# RCShield-v3.net
KiCad netlist of a schematic drawn in EAGLE
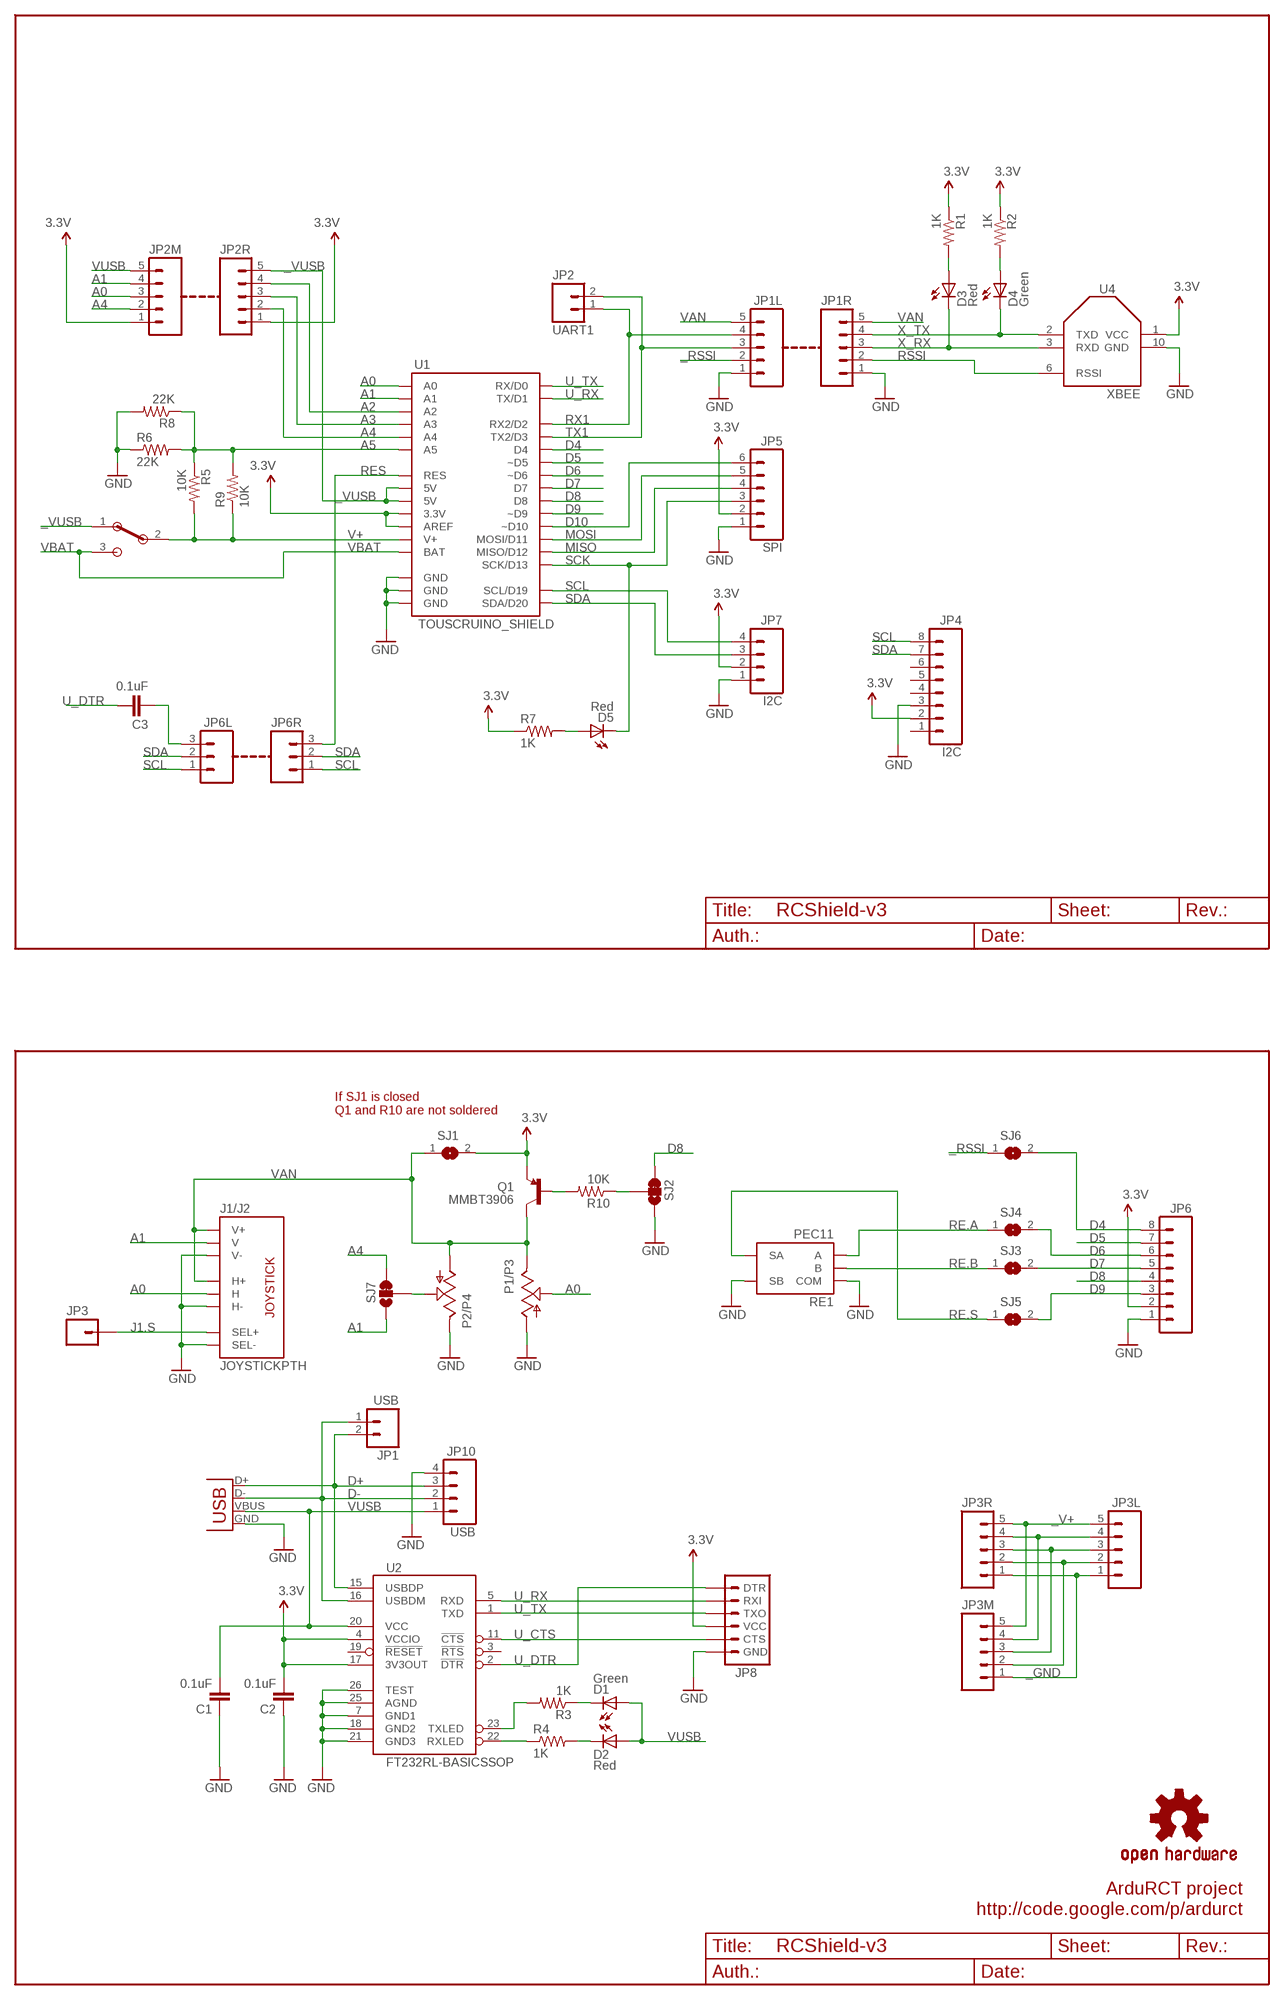
[diagram p0: schematic, sheet 1]

(export (version "E")
  (design (tool "Eeschema 10.0.6"))
  (components
    (comp (ref "C1")
      (value "0.1uF")
      (footprint "eagle-import:0805")
      (libsource (lib "eagle-import") (part "CAP0805"))
    )
    (comp (ref "C2")
      (value "0.1uF")
      (footprint "eagle-import:0805")
      (libsource (lib "eagle-import") (part "CAP0805"))
    )
    (comp (ref "C3")
      (value "0.1uF")
      (footprint "eagle-import:0805")
      (libsource (lib "eagle-import") (part "CAP0805"))
    )
    (comp (ref "D1")
      (value "Green")
      (footprint "eagle-import:LED")
      (libsource (lib "eagle-import") (part "LED"))
    )
    (comp (ref "D2")
      (value "Red")
      (footprint "eagle-import:LED")
      (libsource (lib "eagle-import") (part "LED"))
    )
    (comp (ref "D3")
      (value "Red")
      (footprint "eagle-import:LED")
      (libsource (lib "eagle-import") (part "LED"))
    )
    (comp (ref "D4")
      (value "Green")
      (footprint "eagle-import:LED")
      (libsource (lib "eagle-import") (part "LED"))
    )
    (comp (ref "D5")
      (value "Red")
      (footprint "eagle-import:LED")
      (libsource (lib "eagle-import") (part "LED"))
    )
    (comp (ref "J1/J2")
      (value "JOYSTICKPTH")
      (footprint "eagle-import:JOYSTICK")
      (libsource (lib "eagle-import") (part "JOYSTICKPTH"))
    )
    (comp (ref "JP1")
      (value "USB")
      (footprint "eagle-import:1X02")
      (libsource (lib "eagle-import") (part "M02"))
    )
    (comp (ref "JP1L")
      (value "M05")
      (footprint "eagle-import:2+3")
      (libsource (lib "eagle-import") (part "M05"))
    )
    (comp (ref "JP1R")
      (value "M05")
      (footprint "eagle-import:2+3")
      (libsource (lib "eagle-import") (part "M05"))
    )
    (comp (ref "JP2")
      (value "UART1")
      (footprint "eagle-import:1X02")
      (libsource (lib "eagle-import") (part "M02"))
    )
    (comp (ref "JP2M")
      (value "M05")
      (footprint "eagle-import:2+3")
      (libsource (lib "eagle-import") (part "M05"))
    )
    (comp (ref "JP2R")
      (value "M05")
      (footprint "eagle-import:2+3")
      (libsource (lib "eagle-import") (part "M05"))
    )
    (comp (ref "JP3")
      (value "M01PTH")
      (footprint "eagle-import:1X01")
      (libsource (lib "eagle-import") (part "M01PTH"))
    )
    (comp (ref "JP3L")
      (value "M05")
      (footprint "eagle-import:2+3")
      (libsource (lib "eagle-import") (part "M05"))
    )
    (comp (ref "JP3M")
      (value "M05")
      (footprint "eagle-import:2+3")
      (libsource (lib "eagle-import") (part "M05"))
    )
    (comp (ref "JP3R")
      (value "M05")
      (footprint "eagle-import:2+3")
      (libsource (lib "eagle-import") (part "M05"))
    )
    (comp (ref "JP4")
      (value "I2C")
      (footprint "eagle-import:1X08")
      (libsource (lib "eagle-import") (part "M08"))
    )
    (comp (ref "JP5")
      (value "SPI")
      (footprint "eagle-import:1X06")
      (libsource (lib "eagle-import") (part "M06SIP"))
    )
    (comp (ref "JP6")
      (value "M08")
      (footprint "eagle-import:1X08")
      (libsource (lib "eagle-import") (part "M08"))
    )
    (comp (ref "JP6L")
      (value "M03PTH")
      (footprint "eagle-import:1X03")
      (libsource (lib "eagle-import") (part "M03PTH"))
    )
    (comp (ref "JP6R")
      (value "M03PTH")
      (footprint "eagle-import:1X03")
      (libsource (lib "eagle-import") (part "M03PTH"))
    )
    (comp (ref "JP7")
      (value "I2C")
      (footprint "eagle-import:1X04")
      (libsource (lib "eagle-import") (part "M04"))
    )
    (comp (ref "JP8")
      (value "ARDUINO_SERIAL_PROGRAM")
      (footprint "eagle-import:1X06_F")
      (libsource (lib "eagle-import") (part "ARDUINO_SERIAL_PROGRAM"))
    )
    (comp (ref "JP10")
      (value "USB")
      (footprint "eagle-import:1X04")
      (libsource (lib "eagle-import") (part "M04"))
    )
    (comp (ref "P1/P3")
      (value "POT")
      (footprint "eagle-import:ALPS_POT")
      (libsource (lib "eagle-import") (part "POT"))
    )
    (comp (ref "P2/P4")
      (value "POT")
      (footprint "eagle-import:ALPS_POT")
      (libsource (lib "eagle-import") (part "POT"))
    )
    (comp (ref "Q1")
      (value "MMBT3906")
      (footprint "eagle-import:SOT23-3")
      (libsource (lib "eagle-import") (part "TRANSISTOR_PNPSMD"))
    )
    (comp (ref "R1")
      (value "1K")
      (footprint "eagle-import:0805")
      (libsource (lib "eagle-import") (part "RESISTOR0805-RES"))
    )
    (comp (ref "R2")
      (value "1K")
      (footprint "eagle-import:0805")
      (libsource (lib "eagle-import") (part "RESISTOR0805-RES"))
    )
    (comp (ref "R3")
      (value "1K")
      (footprint "eagle-import:0805")
      (libsource (lib "eagle-import") (part "RESISTOR0805-RES"))
    )
    (comp (ref "R4")
      (value "1K")
      (footprint "eagle-import:0805")
      (libsource (lib "eagle-import") (part "RESISTOR0805-RES"))
    )
    (comp (ref "R5")
      (value "10K")
      (footprint "eagle-import:0805")
      (libsource (lib "eagle-import") (part "RESISTOR0805-RES"))
    )
    (comp (ref "R6")
      (value "22K")
      (footprint "eagle-import:0805")
      (libsource (lib "eagle-import") (part "RESISTOR0805-RES"))
    )
    (comp (ref "R7")
      (value "1K")
      (footprint "eagle-import:0805")
      (libsource (lib "eagle-import") (part "RESISTOR0805-RES"))
    )
    (comp (ref "R8")
      (value "22K")
      (footprint "eagle-import:0207_7")
      (libsource (lib "eagle-import") (part "R-US_0207/7"))
    )
    (comp (ref "R9")
      (value "10K")
      (footprint "eagle-import:0207_7")
      (libsource (lib "eagle-import") (part "R-US_0207/7"))
    )
    (comp (ref "R10")
      (value "10K")
      (footprint "eagle-import:0805")
      (libsource (lib "eagle-import") (part "RESISTOR0805-RES"))
    )
    (comp (ref "RE1")
      (value "PEC11")
      (footprint "eagle-import:PEC11")
      (libsource (lib "eagle-import") (part "PEC11"))
    )
    (comp (ref "S4")
      (value "EG1224")
      (footprint "eagle-import:EG1224")
      (libsource (lib "eagle-import") (part "EG1224"))
    )
    (comp (ref "SJ1")
      (value "SJ")
      (footprint "eagle-import:SJ")
      (libsource (lib "eagle-import") (part "wibauxl_SJ"))
    )
    (comp (ref "SJ2")
      (value "SJ_2WAYS_1-2W")
      (footprint "eagle-import:SJ_2WAYS_1-2")
      (libsource (lib "eagle-import") (part "SJ_2WAYS_1-2W"))
    )
    (comp (ref "SJ3") (value "SJ") (footprint "eagle-import:SJ") (libsource (lib "eagle-import") (part "SJ")))
    (comp (ref "SJ4") (value "SJ") (footprint "eagle-import:SJ") (libsource (lib "eagle-import") (part "SJ")))
    (comp (ref "SJ5") (value "SJ") (footprint "eagle-import:SJ") (libsource (lib "eagle-import") (part "SJ")))
    (comp (ref "SJ6") (value "SJ") (footprint "eagle-import:SJ") (libsource (lib "eagle-import") (part "SJ")))
    (comp (ref "SJ7")
      (value "SJ_2WAYS_1-2W")
      (footprint "eagle-import:SJ_2WAYS_1-2")
      (libsource (lib "eagle-import") (part "SJ_2WAYS_1-2W"))
    )
    (comp (ref "U$1")
      (value "OSHW-LOGOM")
      (footprint "eagle-import:OSHW-LOGO-M")
      (libsource (lib "eagle-import") (part "OSHW-LOGOM"))
    )
    (comp (ref "U1")
      (value "TOUSCRUINO_SHIELD")
      (footprint "eagle-import:TOUSCRUINO_SHIELD_SPLIT")
      (libsource (lib "eagle-import") (part "TOUSCRUINO_SHIELDSPLIT"))
    )
    (comp (ref "U2")
      (value "FT232RL-BASICSSOP")
      (footprint "eagle-import:SSOP28DB")
      (libsource (lib "eagle-import") (part "FT232RL-BASICSSOP"))
    )
    (comp (ref "U4")
      (value "XBEE")
      (footprint "eagle-import:XBEE-SMD")
      (libsource (lib "eagle-import") (part "XBEE-RSSI"))
    )
    (comp (ref "X1")
      (value "USB")
      (footprint "eagle-import:USB-MICROB")
      (libsource (lib "eagle-import") (part "USB"))
    )
  )
  (nets
    (net (code "1") (name "/A0") (class "Default")
      (node (ref "J1/J2") (pin "H2") (pinfunction "H_H2") (pintype "bidirectional"))
      (node (ref "JP2M") (pin "3") (pinfunction "3_3") (pintype "passive"))
      (node (ref "P1/P3") (pin "P$2") (pinfunction "S_P$2") (pintype "passive"))
      (node (ref "U1") (pin "A0") (pinfunction "A0_A0") (pintype "bidirectional"))
    )
    (net (code "2") (name "/A1") (class "Default")
      (node (ref "J1/J2") (pin "V2") (pinfunction "V_V2") (pintype "bidirectional"))
      (node (ref "JP2M") (pin "4") (pinfunction "4_4") (pintype "passive"))
      (node (ref "SJ7") (pin "3") (pinfunction "3_3") (pintype "passive"))
      (node (ref "U1") (pin "A1") (pinfunction "A1_A1") (pintype "bidirectional"))
    )
    (net (code "3") (name "/A2") (class "Default")
      (node (ref "JP2R") (pin "4") (pinfunction "4_4") (pintype "passive"))
      (node (ref "U1") (pin "A2") (pinfunction "A2_A2") (pintype "bidirectional"))
    )
    (net (code "4") (name "/A3") (class "Default")
      (node (ref "JP2R") (pin "3") (pinfunction "3_3") (pintype "passive"))
      (node (ref "U1") (pin "A3") (pinfunction "A3_A3") (pintype "bidirectional"))
    )
    (net (code "5") (name "/A4") (class "Default")
      (node (ref "JP2M") (pin "2") (pinfunction "2_2") (pintype "passive"))
      (node (ref "JP2R") (pin "2") (pinfunction "2_2") (pintype "passive"))
      (node (ref "SJ7") (pin "1") (pinfunction "1_1") (pintype "passive"))
      (node (ref "U1") (pin "A4") (pinfunction "A4_A4") (pintype "bidirectional"))
    )
    (net (code "6") (name "/A5") (class "Default")
      (node (ref "R5") (pin "1") (pinfunction "1_1") (pintype "passive"))
      (node (ref "R6") (pin "2") (pinfunction "2_2") (pintype "passive"))
      (node (ref "R8") (pin "1") (pinfunction "1_1") (pintype "passive"))
      (node (ref "R9") (pin "2") (pinfunction "2_2") (pintype "passive"))
      (node (ref "U1") (pin "A5") (pinfunction "A5_A5") (pintype "bidirectional"))
    )
    (net (code "7") (name "/D+") (class "Default")
      (node (ref "JP1") (pin "2") (pinfunction "2_2") (pintype "passive"))
      (node (ref "JP10") (pin "3") (pinfunction "3_3") (pintype "passive"))
      (node (ref "U2") (pin "15") (pinfunction "USBDP_15") (pintype "bidirectional"))
      (node (ref "X1") (pin "D+") (pinfunction "D+_D+") (pintype "bidirectional"))
    )
    (net (code "8") (name "/D-") (class "Default")
      (node (ref "JP1") (pin "1") (pinfunction "1_1") (pintype "passive"))
      (node (ref "JP10") (pin "2") (pinfunction "2_2") (pintype "passive"))
      (node (ref "U2") (pin "16") (pinfunction "USBDM_16") (pintype "bidirectional"))
      (node (ref "X1") (pin "D-") (pinfunction "D-_D-") (pintype "bidirectional"))
    )
    (net (code "9") (name "/D4") (class "Default")
      (node (ref "JP6") (pin "8") (pinfunction "8_8") (pintype "passive"))
      (node (ref "SJ6") (pin "2") (pinfunction "2_2") (pintype "passive"))
      (node (ref "U1") (pin "D4") (pinfunction "D4_D4") (pintype "bidirectional"))
    )
    (net (code "10") (name "/D5") (class "Default")
      (node (ref "JP6") (pin "7") (pinfunction "7_7") (pintype "passive"))
      (node (ref "U1") (pin "D5") (pinfunction "~{D5}_D5") (pintype "bidirectional"))
    )
    (net (code "11") (name "/D6") (class "Default")
      (node (ref "JP6") (pin "6") (pinfunction "6_6") (pintype "passive"))
      (node (ref "SJ4") (pin "2") (pinfunction "2_2") (pintype "passive"))
      (node (ref "U1") (pin "D6") (pinfunction "~{D6}_D6") (pintype "bidirectional"))
    )
    (net (code "12") (name "/D7") (class "Default")
      (node (ref "JP6") (pin "5") (pinfunction "5_5") (pintype "passive"))
      (node (ref "SJ3") (pin "2") (pinfunction "2_2") (pintype "passive"))
      (node (ref "U1") (pin "D7") (pinfunction "D7_D7") (pintype "bidirectional"))
    )
    (net (code "13") (name "/D8") (class "Default")
      (node (ref "JP6") (pin "4") (pinfunction "4_4") (pintype "passive"))
      (node (ref "SJ2") (pin "1") (pinfunction "1_1") (pintype "passive"))
      (node (ref "U1") (pin "D8") (pinfunction "D8_D8") (pintype "bidirectional"))
    )
    (net (code "14") (name "/D9") (class "Default")
      (node (ref "JP6") (pin "3") (pinfunction "3_3") (pintype "passive"))
      (node (ref "SJ5") (pin "2") (pinfunction "2_2") (pintype "passive"))
      (node (ref "U1") (pin "D9") (pinfunction "~{D9}_D9") (pintype "bidirectional"))
    )
    (net (code "15") (name "/D10") (class "Default")
      (node (ref "JP5") (pin "6") (pinfunction "6_6") (pintype "passive"))
      (node (ref "U1") (pin "D10") (pinfunction "~{D10}_D10") (pintype "bidirectional"))
    )
    (net (code "16") (name "/J1.S") (class "Default")
      (node (ref "J1/J2") (pin "B1A") (pinfunction "SEL+_B1A") (pintype "bidirectional"))
      (node (ref "JP3") (pin "1") (pinfunction "1_1") (pintype "passive"))
    )
    (net (code "17") (name "/MISO") (class "Default")
      (node (ref "JP5") (pin "4") (pinfunction "4_4") (pintype "passive"))
      (node (ref "U1") (pin "D12") (pinfunction "MISO/D12_D12") (pintype "bidirectional"))
    )
    (net (code "18") (name "/MOSI") (class "Default")
      (node (ref "JP5") (pin "5") (pinfunction "5_5") (pintype "passive"))
      (node (ref "U1") (pin "D11") (pinfunction "MOSI/D11_D11") (pintype "bidirectional"))
    )
    (net (code "19") (name "/RE.A") (class "Default")
      (node (ref "RE1") (pin "A") (pinfunction "A_A") (pintype "bidirectional"))
      (node (ref "SJ4") (pin "1") (pinfunction "1_1") (pintype "passive"))
    )
    (net (code "20") (name "/RE.B") (class "Default")
      (node (ref "RE1") (pin "B") (pinfunction "B_B") (pintype "bidirectional"))
      (node (ref "SJ3") (pin "1") (pinfunction "1_1") (pintype "passive"))
    )
    (net (code "21") (name "/RE.S") (class "Default")
      (node (ref "RE1") (pin "S1") (pinfunction "SA_S1") (pintype "bidirectional"))
      (node (ref "SJ5") (pin "1") (pinfunction "1_1") (pintype "passive"))
    )
    (net (code "22") (name "/RES") (class "Default")
      (node (ref "JP6R") (pin "3") (pinfunction "3_3") (pintype "passive"))
      (node (ref "U1") (pin "RES") (pinfunction "RES_RES") (pintype "bidirectional"))
    )
    (net (code "23") (name "/RSSI") (class "Default")
      (node (ref "JP1R") (pin "2") (pinfunction "2_2") (pintype "passive"))
      (node (ref "U4") (pin "6") (pinfunction "RSSI_6") (pintype "bidirectional"))
    )
    (net (code "24") (name "/RX1") (class "Default")
      (node (ref "JP1L") (pin "4") (pinfunction "4_4") (pintype "passive"))
      (node (ref "JP2") (pin "1") (pinfunction "1_1") (pintype "passive"))
      (node (ref "U1") (pin "D2") (pinfunction "RX2/D2_D2") (pintype "bidirectional"))
    )
    (net (code "25") (name "/SCK") (class "Default")
      (node (ref "D5") (pin "C1") (pinfunction "C_C1") (pintype "passive"))
      (node (ref "JP5") (pin "3") (pinfunction "3_3") (pintype "passive"))
      (node (ref "U1") (pin "D13") (pinfunction "SCK/D13_D13") (pintype "bidirectional"))
    )
    (net (code "26") (name "/SCL") (class "Default")
      (node (ref "JP4") (pin "8") (pinfunction "8_8") (pintype "passive"))
      (node (ref "JP6L") (pin "1") (pinfunction "1_1") (pintype "passive"))
      (node (ref "JP6R") (pin "1") (pinfunction "1_1") (pintype "passive"))
      (node (ref "JP7") (pin "4") (pinfunction "4_4") (pintype "passive"))
      (node (ref "U1") (pin "SCL") (pinfunction "SCL/D19_SCL") (pintype "bidirectional"))
    )
    (net (code "27") (name "/SDA") (class "Default")
      (node (ref "JP4") (pin "7") (pinfunction "7_7") (pintype "passive"))
      (node (ref "JP6L") (pin "2") (pinfunction "2_2") (pintype "passive"))
      (node (ref "JP6R") (pin "2") (pinfunction "2_2") (pintype "passive"))
      (node (ref "JP7") (pin "3") (pinfunction "3_3") (pintype "passive"))
      (node (ref "U1") (pin "SDA") (pinfunction "SDA/D20_SDA") (pintype "bidirectional"))
    )
    (net (code "28") (name "/TX1") (class "Default")
      (node (ref "JP1L") (pin "3") (pinfunction "3_3") (pintype "passive"))
      (node (ref "JP2") (pin "2") (pinfunction "2_2") (pintype "passive"))
      (node (ref "U1") (pin "D3") (pinfunction "TX2/D3_D3") (pintype "bidirectional"))
    )
    (net (code "29") (name "/U_CTS") (class "Default")
      (node (ref "JP8") (pin "5") (pinfunction "CTS_5") (pintype "passive"))
      (node (ref "U2") (pin "11") (pinfunction "~{CTS}_11") (pintype "bidirectional"))
    )
    (net (code "30") (name "/U_DTR") (class "Default")
      (node (ref "C3") (pin "1") (pinfunction "1_1") (pintype "passive"))
      (node (ref "JP8") (pin "1") (pinfunction "DTR_1") (pintype "passive"))
      (node (ref "U2") (pin "2") (pinfunction "~{DTR}_2") (pintype "bidirectional"))
    )
    (net (code "31") (name "/U_RX") (class "Default")
      (node (ref "JP8") (pin "2") (pinfunction "RXI_2") (pintype "passive"))
      (node (ref "U1") (pin "TX") (pinfunction "TX/D1_TX") (pintype "bidirectional"))
      (node (ref "U2") (pin "5") (pinfunction "RXD_5") (pintype "input"))
    )
    (net (code "32") (name "/U_TX") (class "Default")
      (node (ref "JP8") (pin "3") (pinfunction "TXO_3") (pintype "passive"))
      (node (ref "U1") (pin "RX") (pinfunction "RX/D0_RX") (pintype "bidirectional"))
      (node (ref "U2") (pin "1") (pinfunction "TXD_1") (pintype "output"))
    )
    (net (code "33") (name "/V+") (class "Default")
      (node (ref "R5") (pin "2") (pinfunction "2_2") (pintype "passive"))
      (node (ref "R9") (pin "1") (pinfunction "1_1") (pintype "passive"))
      (node (ref "S4") (pin "2") (pinfunction "2_2") (pintype "bidirectional"))
      (node (ref "U1") (pin "V+") (pinfunction "V+_V+") (pintype "bidirectional"))
    )
    (net (code "34") (name "/VAN") (class "Default")
      (node (ref "J1/J2") (pin "H1") (pinfunction "H+_H1") (pintype "bidirectional"))
      (node (ref "J1/J2") (pin "V1") (pinfunction "V+_V1") (pintype "bidirectional"))
      (node (ref "JP1L") (pin "5") (pinfunction "5_5") (pintype "passive"))
      (node (ref "JP1R") (pin "5") (pinfunction "5_5") (pintype "passive"))
      (node (ref "P1/P3") (pin "P$1") (pinfunction "E_P$1") (pintype "passive"))
      (node (ref "P2/P4") (pin "P$3") (pinfunction "A_P$3") (pintype "passive"))
      (node (ref "Q1") (pin "3") (pinfunction "C_3") (pintype "passive"))
      (node (ref "SJ1") (pin "1") (pinfunction "1_1") (pintype "passive"))
    )
    (net (code "35") (name "/VBAT") (class "Default")
      (node (ref "S4") (pin "3") (pinfunction "3_3") (pintype "bidirectional"))
      (node (ref "U1") (pin "BAT") (pinfunction "BAT_BAT") (pintype "bidirectional"))
    )
    (net (code "36") (name "/VUSB") (class "Default")
      (node (ref "C1") (pin "2") (pinfunction "2_2") (pintype "passive"))
      (node (ref "D1") (pin "A1") (pinfunction "A_A1") (pintype "passive"))
      (node (ref "D2") (pin "A1") (pinfunction "A_A1") (pintype "passive"))
      (node (ref "JP10") (pin "1") (pinfunction "1_1") (pintype "passive"))
      (node (ref "JP2M") (pin "5") (pinfunction "5_5") (pintype "passive"))
      (node (ref "U2") (pin "20") (pinfunction "VCC_20") (pintype "bidirectional"))
      (node (ref "X1") (pin "VBUS") (pinfunction "VBUS_VBUS") (pintype "bidirectional"))
    )
    (net (code "37") (name "/X_RX") (class "Default")
      (node (ref "D3") (pin "C1") (pinfunction "C_C1") (pintype "passive"))
      (node (ref "JP1R") (pin "3") (pinfunction "3_3") (pintype "passive"))
      (node (ref "U4") (pin "3") (pinfunction "RXD_3") (pintype "bidirectional"))
    )
    (net (code "38") (name "/X_TX") (class "Default")
      (node (ref "D4") (pin "C1") (pinfunction "C_C1") (pintype "passive"))
      (node (ref "JP1R") (pin "4") (pinfunction "4_4") (pintype "passive"))
      (node (ref "U4") (pin "2") (pinfunction "TXD_2") (pintype "bidirectional"))
    )
    (net (code "39") (name "/_GND") (class "Default")
      (node (ref "JP3L") (pin "1") (pinfunction "1_1") (pintype "passive"))
      (node (ref "JP3M") (pin "1") (pinfunction "1_1") (pintype "passive"))
      (node (ref "JP3R") (pin "1") (pinfunction "1_1") (pintype "passive"))
    )
    (net (code "40") (name "/_RSSI") (class "Default")
      (node (ref "JP1L") (pin "2") (pinfunction "2_2") (pintype "passive"))
      (node (ref "SJ6") (pin "1") (pinfunction "1_1") (pintype "passive"))
    )
    (net (code "41") (name "/_V+") (class "Default")
      (node (ref "JP3L") (pin "5") (pinfunction "5_5") (pintype "passive"))
      (node (ref "JP3M") (pin "5") (pinfunction "5_5") (pintype "passive"))
      (node (ref "JP3R") (pin "5") (pinfunction "5_5") (pintype "passive"))
    )
    (net (code "42") (name "/_VUSB") (class "Default")
      (node (ref "JP2R") (pin "5") (pinfunction "5_5") (pintype "passive"))
      (node (ref "S4") (pin "1") (pinfunction "1_1") (pintype "bidirectional"))
      (node (ref "U1") (pin "5V@0") (pinfunction "5V_5V@0") (pintype "bidirectional"))
      (node (ref "U1") (pin "5V@1") (pinfunction "5V_5V@1") (pintype "bidirectional"))
    )
    (net (code "43") (name "3.3V") (class "Default")
      (node (ref "C2") (pin "2") (pinfunction "2_2") (pintype "passive"))
      (node (ref "JP2M") (pin "1") (pinfunction "1_1") (pintype "passive"))
      (node (ref "JP2R") (pin "1") (pinfunction "1_1") (pintype "passive"))
      (node (ref "JP4") (pin "2") (pinfunction "2_2") (pintype "passive"))
      (node (ref "JP5") (pin "2") (pinfunction "2_2") (pintype "passive"))
      (node (ref "JP6") (pin "2") (pinfunction "2_2") (pintype "passive"))
      (node (ref "JP7") (pin "2") (pinfunction "2_2") (pintype "passive"))
      (node (ref "JP8") (pin "4") (pinfunction "VCC_4") (pintype "passive"))
      (node (ref "Q1") (pin "2") (pinfunction "E_2") (pintype "passive"))
      (node (ref "R1") (pin "1") (pinfunction "1_1") (pintype "passive"))
      (node (ref "R2") (pin "1") (pinfunction "1_1") (pintype "passive"))
      (node (ref "R7") (pin "1") (pinfunction "1_1") (pintype "passive"))
      (node (ref "SJ1") (pin "2") (pinfunction "2_2") (pintype "passive"))
      (node (ref "U1") (pin "3.3V") (pinfunction "3.3V_3.3V") (pintype "bidirectional"))
      (node (ref "U1") (pin "AREF") (pinfunction "AREF_AREF") (pintype "bidirectional"))
      (node (ref "U2") (pin "17") (pinfunction "3V3OUT_17") (pintype "output"))
      (node (ref "U2") (pin "4") (pinfunction "VCCIO_4") (pintype "bidirectional"))
      (node (ref "U4") (pin "1") (pinfunction "VCC_1") (pintype "bidirectional"))
    )
    (net (code "44") (name "GND") (class "Default")
      (node (ref "C1") (pin "1") (pinfunction "1_1") (pintype "passive"))
      (node (ref "C2") (pin "1") (pinfunction "1_1") (pintype "passive"))
      (node (ref "J1/J2") (pin "B2A") (pinfunction "SEL-_B2A") (pintype "bidirectional"))
      (node (ref "J1/J2") (pin "H3") (pinfunction "H-_H3") (pintype "bidirectional"))
      (node (ref "J1/J2") (pin "V3") (pinfunction "V-_V3") (pintype "bidirectional"))
      (node (ref "JP10") (pin "4") (pinfunction "4_4") (pintype "passive"))
      (node (ref "JP1L") (pin "1") (pinfunction "1_1") (pintype "passive"))
      (node (ref "JP1R") (pin "1") (pinfunction "1_1") (pintype "passive"))
      (node (ref "JP4") (pin "3") (pinfunction "3_3") (pintype "passive"))
      (node (ref "JP5") (pin "1") (pinfunction "1_1") (pintype "passive"))
      (node (ref "JP6") (pin "1") (pinfunction "1_1") (pintype "passive"))
      (node (ref "JP7") (pin "1") (pinfunction "1_1") (pintype "passive"))
      (node (ref "JP8") (pin "6") (pinfunction "GND_6") (pintype "passive"))
      (node (ref "P1/P3") (pin "P$3") (pinfunction "A_P$3") (pintype "passive"))
      (node (ref "P2/P4") (pin "P$1") (pinfunction "E_P$1") (pintype "passive"))
      (node (ref "R6") (pin "1") (pinfunction "1_1") (pintype "passive"))
      (node (ref "R8") (pin "2") (pinfunction "2_2") (pintype "passive"))
      (node (ref "RE1") (pin "C") (pinfunction "COM_C") (pintype "bidirectional"))
      (node (ref "RE1") (pin "S2") (pinfunction "SB_S2") (pintype "bidirectional"))
      (node (ref "SJ2") (pin "3") (pinfunction "3_3") (pintype "passive"))
      (node (ref "U1") (pin "GND@0") (pinfunction "GND_GND@0") (pintype "bidirectional"))
      (node (ref "U1") (pin "GND@1") (pinfunction "GND_GND@1") (pintype "bidirectional"))
      (node (ref "U1") (pin "GND@2") (pinfunction "GND_GND@2") (pintype "bidirectional"))
      (node (ref "U2") (pin "18") (pinfunction "GND2_18") (pintype "bidirectional"))
      (node (ref "U2") (pin "21") (pinfunction "GND3_21") (pintype "bidirectional"))
      (node (ref "U2") (pin "25") (pinfunction "AGND_25") (pintype "bidirectional"))
      (node (ref "U2") (pin "26") (pinfunction "TEST_26") (pintype "input"))
      (node (ref "U2") (pin "7") (pinfunction "GND1_7") (pintype "bidirectional"))
      (node (ref "U4") (pin "10") (pinfunction "GND_10") (pintype "bidirectional"))
      (node (ref "X1") (pin "GND") (pinfunction "GND_GND") (pintype "bidirectional"))
    )
    (net (code "45") (name "Net-(C3-Pad2)") (class "Default")
      (node (ref "C3") (pin "2") (pinfunction "2_2") (pintype "passive"))
      (node (ref "JP6L") (pin "3") (pinfunction "3_3") (pintype "passive"))
    )
    (net (code "46") (name "Net-(D1-C)") (class "Default")
      (node (ref "D1") (pin "C1") (pinfunction "C_C1") (pintype "passive"))
      (node (ref "R3") (pin "1") (pinfunction "1_1") (pintype "passive"))
    )
    (net (code "47") (name "Net-(D2-C)") (class "Default")
      (node (ref "D2") (pin "C1") (pinfunction "C_C1") (pintype "passive"))
      (node (ref "R4") (pin "2") (pinfunction "2_2") (pintype "passive"))
    )
    (net (code "48") (name "Net-(D3-A)") (class "Default")
      (node (ref "D3") (pin "A1") (pinfunction "A_A1") (pintype "passive"))
      (node (ref "R1") (pin "2") (pinfunction "2_2") (pintype "passive"))
    )
    (net (code "49") (name "Net-(D4-A)") (class "Default")
      (node (ref "D4") (pin "A1") (pinfunction "A_A1") (pintype "passive"))
      (node (ref "R2") (pin "2") (pinfunction "2_2") (pintype "passive"))
    )
    (net (code "50") (name "Net-(D5-A)") (class "Default")
      (node (ref "D5") (pin "A1") (pinfunction "A_A1") (pintype "passive"))
      (node (ref "R7") (pin "2") (pinfunction "2_2") (pintype "passive"))
    )
    (net (code "51") (name "Net-(JP3L-Pad2)") (class "Default")
      (node (ref "JP3L") (pin "2") (pinfunction "2_2") (pintype "passive"))
      (node (ref "JP3M") (pin "2") (pinfunction "2_2") (pintype "passive"))
      (node (ref "JP3R") (pin "2") (pinfunction "2_2") (pintype "passive"))
    )
    (net (code "52") (name "Net-(JP3L-Pad3)") (class "Default")
      (node (ref "JP3L") (pin "3") (pinfunction "3_3") (pintype "passive"))
      (node (ref "JP3M") (pin "3") (pinfunction "3_3") (pintype "passive"))
      (node (ref "JP3R") (pin "3") (pinfunction "3_3") (pintype "passive"))
    )
    (net (code "53") (name "Net-(JP3L-Pad4)") (class "Default")
      (node (ref "JP3L") (pin "4") (pinfunction "4_4") (pintype "passive"))
      (node (ref "JP3M") (pin "4") (pinfunction "4_4") (pintype "passive"))
      (node (ref "JP3R") (pin "4") (pinfunction "4_4") (pintype "passive"))
    )
    (net (code "54") (name "Net-(P2/P4-S)") (class "Default")
      (node (ref "P2/P4") (pin "P$2") (pinfunction "S_P$2") (pintype "passive"))
      (node (ref "SJ7") (pin "2") (pinfunction "2_2") (pintype "passive"))
    )
    (net (code "55") (name "Net-(Q1-B)") (class "Default")
      (node (ref "Q1") (pin "1") (pinfunction "B_1") (pintype "passive"))
      (node (ref "R10") (pin "2") (pinfunction "2_2") (pintype "passive"))
    )
    (net (code "56") (name "Net-(R10-Pad1)") (class "Default")
      (node (ref "R10") (pin "1") (pinfunction "1_1") (pintype "passive"))
      (node (ref "SJ2") (pin "2") (pinfunction "2_2") (pintype "passive"))
    )
    (net (code "57") (name "Net-(U2-RXLED)") (class "Default")
      (node (ref "R4") (pin "1") (pinfunction "1_1") (pintype "passive"))
      (node (ref "U2") (pin "22") (pinfunction "RXLED_22") (pintype "bidirectional"))
    )
    (net (code "58") (name "Net-(U2-TXLED)") (class "Default")
      (node (ref "R3") (pin "2") (pinfunction "2_2") (pintype "passive"))
      (node (ref "U2") (pin "23") (pinfunction "TXLED_23") (pintype "bidirectional"))
    )
    (net (code "59") (name "unconnected-(JP4-Pad1)") (class "Default")
      (node (ref "JP4") (pin "1") (pinfunction "1_1") (pintype "passive"))
    )
    (net (code "60") (name "unconnected-(JP4-Pad4)") (class "Default")
      (node (ref "JP4") (pin "4") (pinfunction "4_4") (pintype "passive"))
    )
    (net (code "61") (name "unconnected-(JP4-Pad5)") (class "Default")
      (node (ref "JP4") (pin "5") (pinfunction "5_5") (pintype "passive"))
    )
    (net (code "62") (name "unconnected-(JP4-Pad6)") (class "Default")
      (node (ref "JP4") (pin "6") (pinfunction "6_6") (pintype "passive"))
    )
    (net (code "63") (name "unconnected-(U2-~{RESET}-Pad19)") (class "Default")
      (node (ref "U2") (pin "19") (pinfunction "~{RESET}_19") (pintype "bidirectional"))
    )
    (net (code "64") (name "unconnected-(U2-~{RTS}-Pad3)") (class "Default")
      (node (ref "U2") (pin "3") (pinfunction "~{RTS}_3") (pintype "bidirectional"))
    )
  )
)
